# optical_sensor_prototype.net
KiCad netlist of a schematic drawn in EAGLE
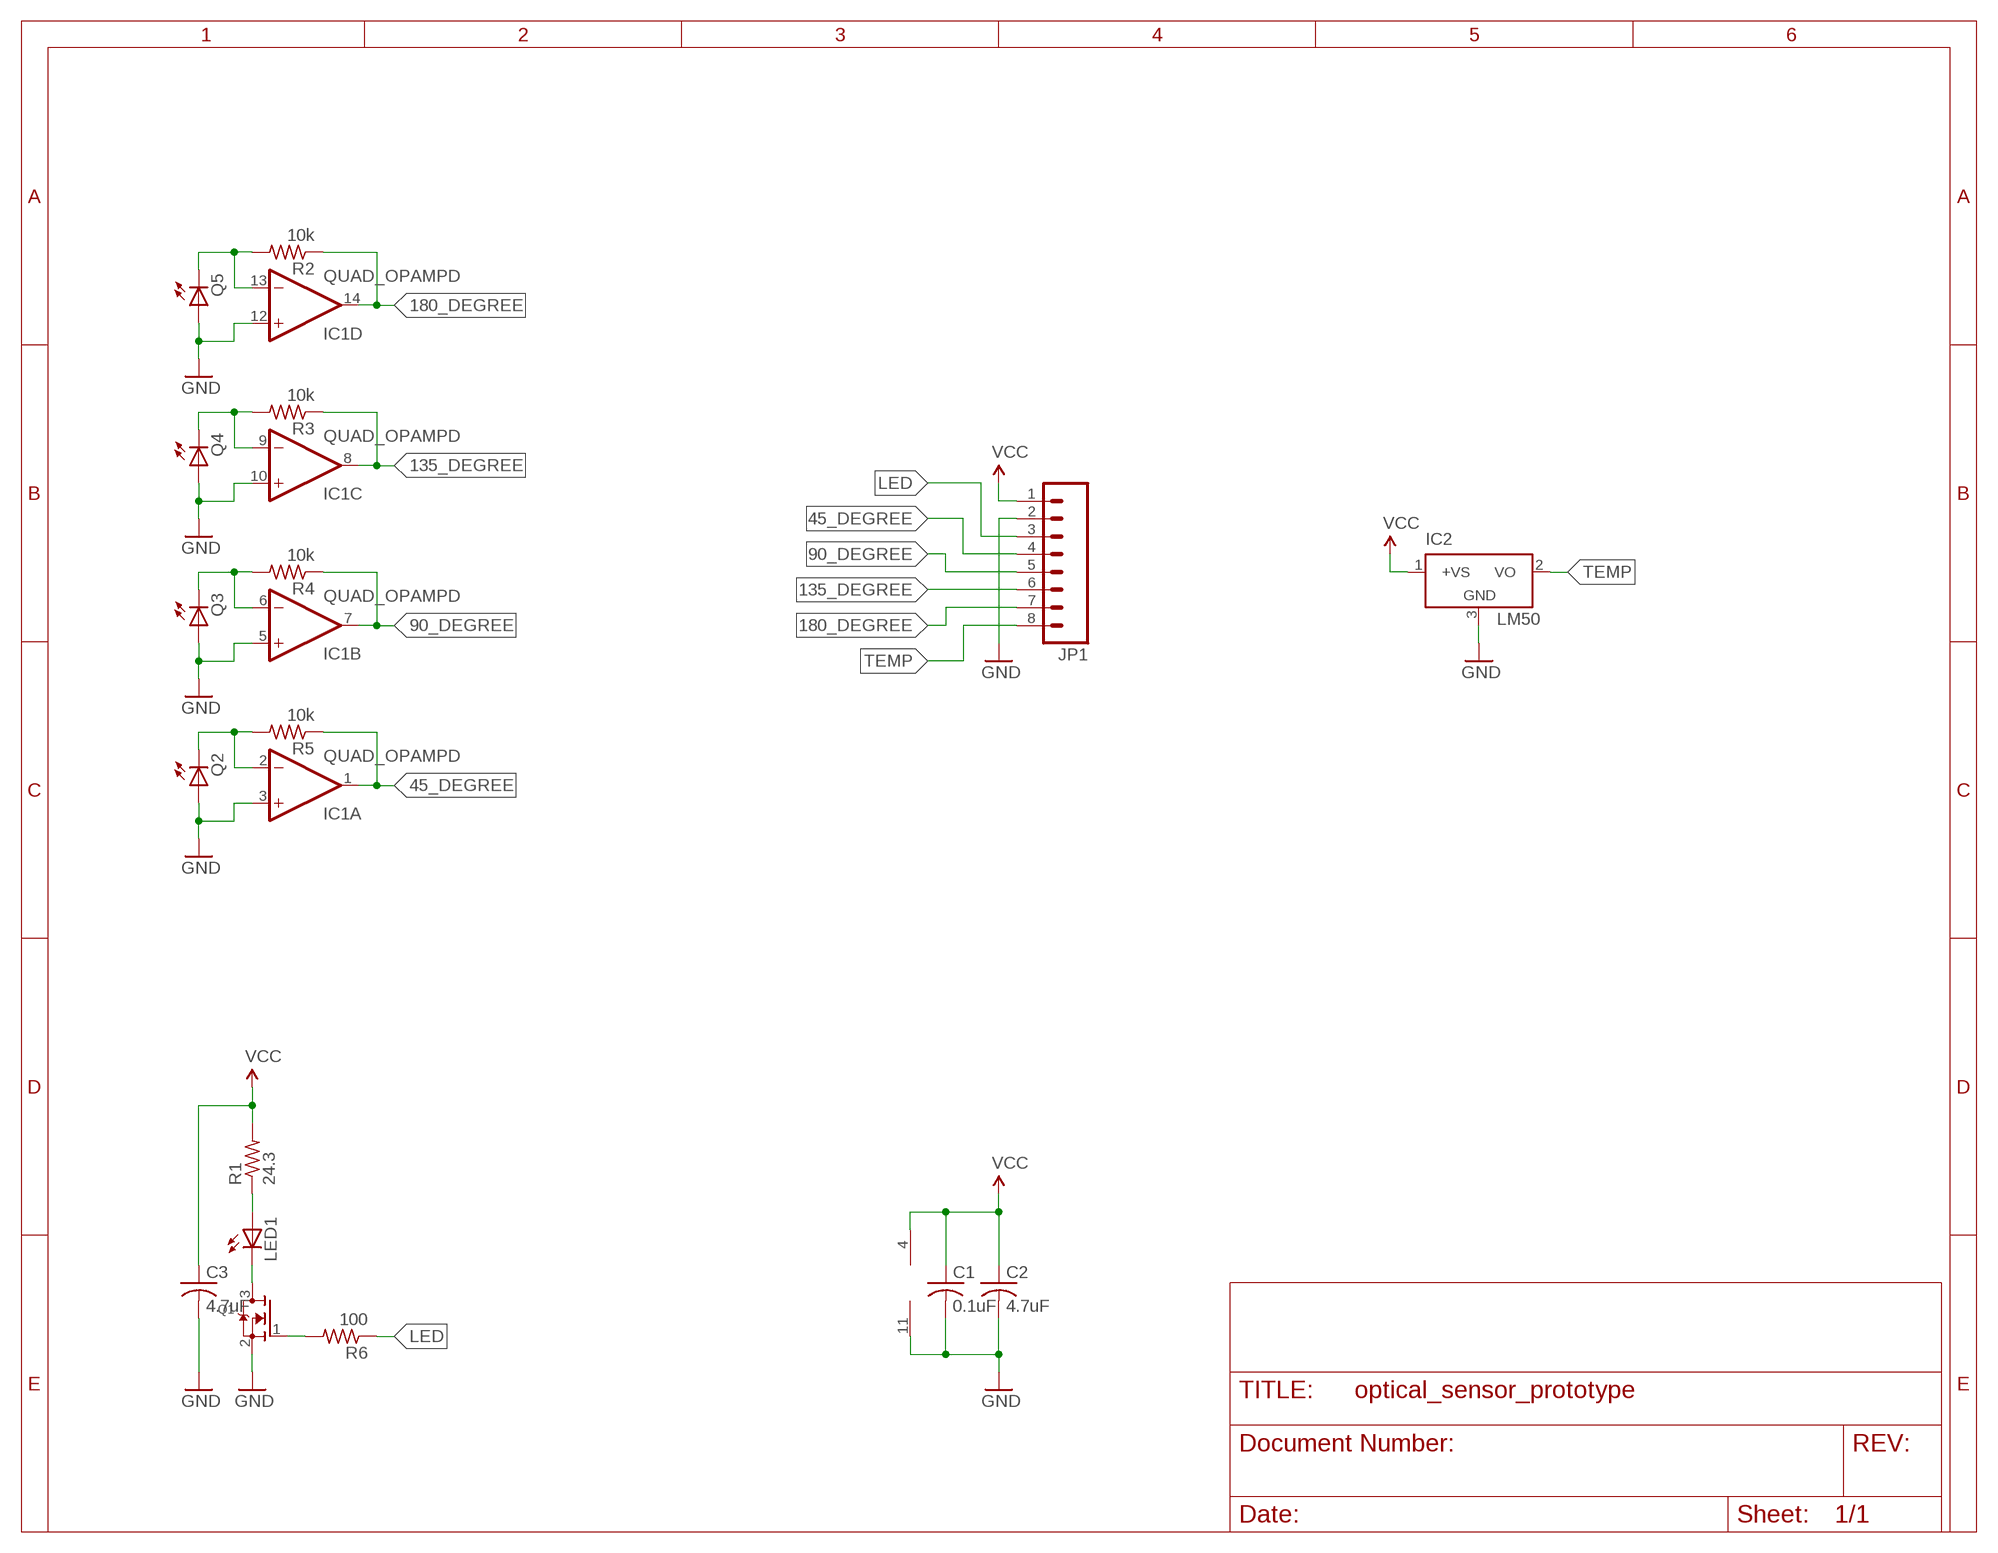
[diagram p0: schematic, sheet 1]

(export (version "E")
  (design (tool "Eeschema 10.0.6"))
  (components
    (comp (ref "C1")
      (value "0.1uF")
      (footprint "eagle-import:C1206")
      (libsource (lib "eagle-import") (part "C-USC1206"))
    )
    (comp (ref "C2")
      (value "4.7uF")
      (footprint "eagle-import:C1206")
      (libsource (lib "eagle-import") (part "C-USC1206"))
    )
    (comp (ref "C3")
      (value "4.7uF")
      (footprint "eagle-import:C1206")
      (libsource (lib "eagle-import") (part "C-USC1206"))
    )
    (comp (ref "IC1")
      (value "QUAD_OPAMPD")
      (footprint "eagle-import:SO14")
      (libsource (lib "eagle-import") (part "QUAD_OPAMPD"))
    )
    (comp (ref "IC2")
      (value "LM50")
      (footprint "eagle-import:SOT23")
      (libsource (lib "eagle-import") (part "LM50"))
    )
    (comp (ref "JP1")
      (value "M081X08")
      (footprint "eagle-import:1X08")
      (libsource (lib "eagle-import") (part "M081X08"))
    )
    (comp (ref "LED1")
      (value "LEDSMT1206")
      (footprint "eagle-import:1206")
      (libsource (lib "eagle-import") (part "LEDSMT1206"))
    )
    (comp (ref "Q1")
      (value "MOSFET-NREFLOW")
      (footprint "eagle-import:SOT23")
      (libsource (lib "eagle-import") (part "MOSFET-NREFLOW"))
    )
    (comp (ref "Q2")
      (value "LEDSMT1206")
      (footprint "eagle-import:1206")
      (libsource (lib "eagle-import") (part "LEDSMT1206"))
    )
    (comp (ref "Q3")
      (value "LEDSMT1206")
      (footprint "eagle-import:1206")
      (libsource (lib "eagle-import") (part "LEDSMT1206"))
    )
    (comp (ref "Q4")
      (value "LEDSMT1206")
      (footprint "eagle-import:1206")
      (libsource (lib "eagle-import") (part "LEDSMT1206"))
    )
    (comp (ref "Q5")
      (value "LEDSMT1206")
      (footprint "eagle-import:1206")
      (libsource (lib "eagle-import") (part "LEDSMT1206"))
    )
    (comp (ref "R1")
      (value "24.3")
      (footprint "eagle-import:R1206")
      (libsource (lib "eagle-import") (part "R-US_R1206"))
    )
    (comp (ref "R2")
      (value "10k")
      (footprint "eagle-import:R1206")
      (libsource (lib "eagle-import") (part "R-US_R1206"))
    )
    (comp (ref "R3")
      (value "10k")
      (footprint "eagle-import:R1206")
      (libsource (lib "eagle-import") (part "R-US_R1206"))
    )
    (comp (ref "R4")
      (value "10k")
      (footprint "eagle-import:R1206")
      (libsource (lib "eagle-import") (part "R-US_R1206"))
    )
    (comp (ref "R5")
      (value "10k")
      (footprint "eagle-import:R1206")
      (libsource (lib "eagle-import") (part "R-US_R1206"))
    )
    (comp (ref "R6")
      (value "100")
      (footprint "eagle-import:R1206")
      (libsource (lib "eagle-import") (part "R-US_R1206"))
    )
  )
  (nets
    (net (code "1") (name "45_DEGREE") (class "Default")
      (node (ref "IC1") (pin "1") (pinfunction "OUT_1") (pintype "output"))
      (node (ref "JP1") (pin "4") (pinfunction "4_4") (pintype "passive"))
      (node (ref "R5") (pin "1") (pinfunction "1_1") (pintype "passive"))
    )
    (net (code "2") (name "90_DEGREE") (class "Default")
      (node (ref "IC1") (pin "7") (pinfunction "OUT_7") (pintype "output"))
      (node (ref "JP1") (pin "5") (pinfunction "5_5") (pintype "passive"))
      (node (ref "R4") (pin "1") (pinfunction "1_1") (pintype "passive"))
    )
    (net (code "3") (name "135_DEGREE") (class "Default")
      (node (ref "IC1") (pin "8") (pinfunction "OUT_8") (pintype "output"))
      (node (ref "JP1") (pin "6") (pinfunction "6_6") (pintype "passive"))
      (node (ref "R3") (pin "1") (pinfunction "1_1") (pintype "passive"))
    )
    (net (code "4") (name "180_DEGREE") (class "Default")
      (node (ref "IC1") (pin "14") (pinfunction "OUT_14") (pintype "output"))
      (node (ref "JP1") (pin "7") (pinfunction "7_7") (pintype "passive"))
      (node (ref "R2") (pin "1") (pinfunction "1_1") (pintype "passive"))
    )
    (net (code "5") (name "GND") (class "Default")
      (node (ref "C1") (pin "2") (pinfunction "2_2") (pintype "passive"))
      (node (ref "C2") (pin "2") (pinfunction "2_2") (pintype "passive"))
      (node (ref "C3") (pin "2") (pinfunction "2_2") (pintype "passive"))
      (node (ref "IC1") (pin "10") (pinfunction "+IN_10") (pintype "input"))
      (node (ref "IC1") (pin "11") (pinfunction "V-_11") (pintype "power_in"))
      (node (ref "IC1") (pin "12") (pinfunction "+IN_12") (pintype "input"))
      (node (ref "IC1") (pin "3") (pinfunction "+IN_3") (pintype "input"))
      (node (ref "IC1") (pin "5") (pinfunction "+IN_5") (pintype "input"))
      (node (ref "IC2") (pin "3") (pinfunction "GND_3") (pintype "power_in"))
      (node (ref "JP1") (pin "2") (pinfunction "2_2") (pintype "passive"))
      (node (ref "Q1") (pin "2") (pinfunction "S_2") (pintype "bidirectional"))
      (node (ref "Q2") (pin "A") (pinfunction "A_A") (pintype "passive"))
      (node (ref "Q3") (pin "A") (pinfunction "A_A") (pintype "passive"))
      (node (ref "Q4") (pin "A") (pinfunction "A_A") (pintype "passive"))
      (node (ref "Q5") (pin "A") (pinfunction "A_A") (pintype "passive"))
    )
    (net (code "6") (name "LED") (class "Default")
      (node (ref "JP1") (pin "3") (pinfunction "3_3") (pintype "passive"))
      (node (ref "R6") (pin "1") (pinfunction "1_1") (pintype "passive"))
    )
    (net (code "7") (name "Net-(IC1A--IN)") (class "Default")
      (node (ref "IC1") (pin "2") (pinfunction "-IN_2") (pintype "input"))
      (node (ref "Q2") (pin "C") (pinfunction "C_C") (pintype "passive"))
      (node (ref "R5") (pin "2") (pinfunction "2_2") (pintype "passive"))
    )
    (net (code "8") (name "Net-(IC1B--IN)") (class "Default")
      (node (ref "IC1") (pin "6") (pinfunction "-IN_6") (pintype "input"))
      (node (ref "Q3") (pin "C") (pinfunction "C_C") (pintype "passive"))
      (node (ref "R4") (pin "2") (pinfunction "2_2") (pintype "passive"))
    )
    (net (code "9") (name "Net-(IC1C--IN)") (class "Default")
      (node (ref "IC1") (pin "9") (pinfunction "-IN_9") (pintype "input"))
      (node (ref "Q4") (pin "C") (pinfunction "C_C") (pintype "passive"))
      (node (ref "R3") (pin "2") (pinfunction "2_2") (pintype "passive"))
    )
    (net (code "10") (name "Net-(IC1D--IN)") (class "Default")
      (node (ref "IC1") (pin "13") (pinfunction "-IN_13") (pintype "input"))
      (node (ref "Q5") (pin "C") (pinfunction "C_C") (pintype "passive"))
      (node (ref "R2") (pin "2") (pinfunction "2_2") (pintype "passive"))
    )
    (net (code "11") (name "Net-(LED1-PadA)") (class "Default")
      (node (ref "LED1") (pin "A") (pinfunction "A_A") (pintype "passive"))
      (node (ref "R1") (pin "1") (pinfunction "1_1") (pintype "passive"))
    )
    (net (code "12") (name "Net-(Q1-D)") (class "Default")
      (node (ref "LED1") (pin "C") (pinfunction "C_C") (pintype "passive"))
      (node (ref "Q1") (pin "3") (pinfunction "D_3") (pintype "bidirectional"))
    )
    (net (code "13") (name "Net-(Q1-G)") (class "Default")
      (node (ref "Q1") (pin "1") (pinfunction "G_1") (pintype "bidirectional"))
      (node (ref "R6") (pin "2") (pinfunction "2_2") (pintype "passive"))
    )
    (net (code "14") (name "TEMP") (class "Default")
      (node (ref "IC2") (pin "2") (pinfunction "VO_2") (pintype "input"))
      (node (ref "JP1") (pin "8") (pinfunction "8_8") (pintype "passive"))
    )
    (net (code "15") (name "VCC") (class "Default")
      (node (ref "C1") (pin "1") (pinfunction "1_1") (pintype "passive"))
      (node (ref "C2") (pin "1") (pinfunction "1_1") (pintype "passive"))
      (node (ref "C3") (pin "1") (pinfunction "1_1") (pintype "passive"))
      (node (ref "IC1") (pin "4") (pinfunction "V+_4") (pintype "power_in"))
      (node (ref "IC2") (pin "1") (pinfunction "+VS_1") (pintype "input"))
      (node (ref "JP1") (pin "1") (pinfunction "1_1") (pintype "passive"))
      (node (ref "R1") (pin "2") (pinfunction "2_2") (pintype "passive"))
    )
  )
)
